# RK3399_EMMC_ADC_PCIE.net
KiCad netlist of a schematic drawn in Altium Designer
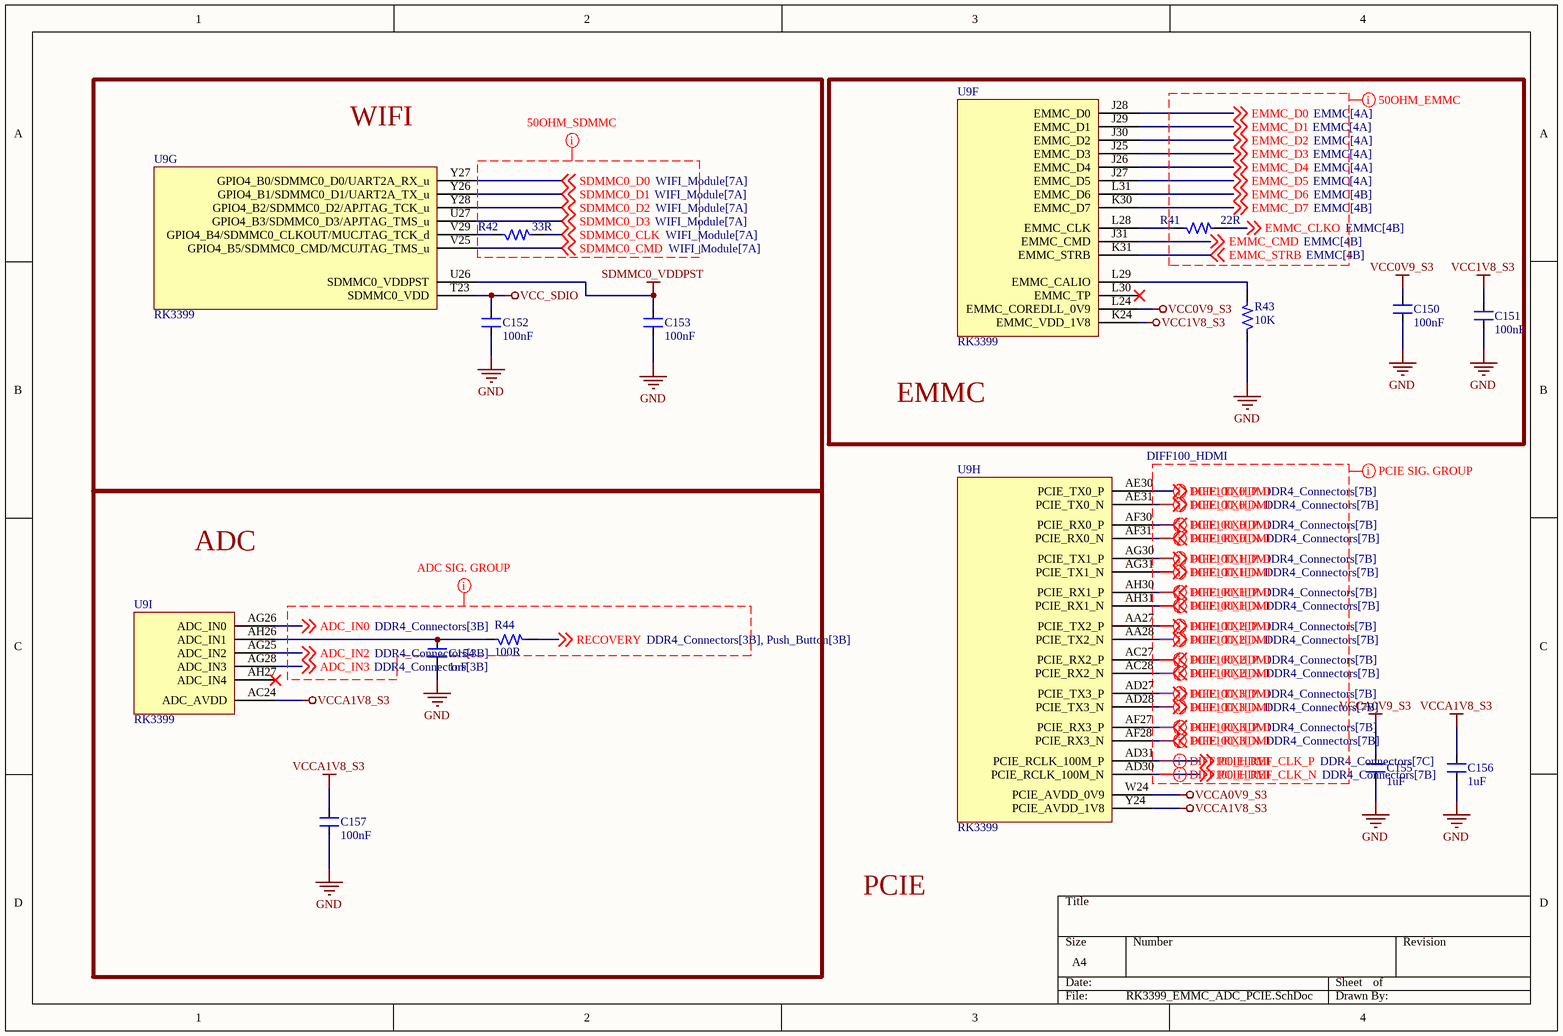
[diagram p0: RK3399_EMMC_ADC_PCIE.SchDoc]

(export (version "E")
  (design (tool "Eeschema 10.0.6"))
  (components
    (comp (ref "C150")
      (value "100nF")
      (footprint "CAP_0201")
      (description "0.1µF ±10% 25V Ceramic Capacitor X5R 0201 (0603 Metric)")
      (fields
        (field (name "MANUFACTURER") "TDK Corporation")
        (field (name "MANUFACTURER PART NUMBER") "C0603X5R1E104K030BB")
      )
      (libsource (lib "EsteemPCB_SOM_Course_schlib") (part "CAP_100nF-25V-10%-0201"))
    )
    (comp (ref "C151")
      (value "100nF")
      (footprint "CAP_0201")
      (description "0.1µF ±10% 25V Ceramic Capacitor X5R 0201 (0603 Metric)")
      (fields
        (field (name "MANUFACTURER") "TDK Corporation")
        (field (name "MANUFACTURER PART NUMBER") "C0603X5R1E104K030BB")
      )
      (libsource (lib "EsteemPCB_SOM_Course_schlib") (part "CAP_100nF-25V-10%-0201"))
    )
    (comp (ref "C152")
      (value "100nF")
      (footprint "CAP_0201")
      (description "0.1µF ±10% 25V Ceramic Capacitor X5R 0201 (0603 Metric)")
      (fields
        (field (name "MANUFACTURER") "TDK Corporation")
        (field (name "MANUFACTURER PART NUMBER") "C0603X5R1E104K030BB")
      )
      (libsource (lib "EsteemPCB_SOM_Course_schlib") (part "CAP_100nF-25V-10%-0201"))
    )
    (comp (ref "C153")
      (value "100nF")
      (footprint "CAP_0201")
      (description "0.1µF ±10% 25V Ceramic Capacitor X5R 0201 (0603 Metric)")
      (fields
        (field (name "MANUFACTURER") "TDK Corporation")
        (field (name "MANUFACTURER PART NUMBER") "C0603X5R1E104K030BB")
      )
      (libsource (lib "EsteemPCB_SOM_Course_schlib") (part "CAP_100nF-25V-10%-0201"))
    )
    (comp (ref "C154")
      (value "1nF")
      (footprint "CAP_0201")
      (description "1000pF ±10% 16V Ceramic Capacitor X7R 0201 (0603 Metric)")
      (fields
        (field (name "MANUFACTURER") "Murata Electronics")
        (field (name "MANUFACTURER PART NUMBER") "GRM033R71C102KA01D")
      )
      (libsource (lib "EsteemPCB_SOM_Course_schlib") (part "CAP_1nF-16V-10%-0201"))
    )
    (comp (ref "C155")
      (value "1uF")
      (footprint "CAP_0201")
      (description "1µF ±20% 16V Ceramic Capacitor X5R 0201 (0603 Metric)")
      (fields
        (field (name "MANUFACTURER") "Samsung Electro-Mechanics")
        (field (name "MANUFACTURER PART NUMBER") "CL03A105MO3NRNH")
      )
      (libsource (lib "EsteemPCB_SOM_Course_schlib") (part "CAP_1uF-16V-10%-0201"))
    )
    (comp (ref "C156")
      (value "1uF")
      (footprint "CAP_0201")
      (description "1µF ±20% 16V Ceramic Capacitor X5R 0201 (0603 Metric)")
      (fields
        (field (name "MANUFACTURER") "Samsung Electro-Mechanics")
        (field (name "MANUFACTURER PART NUMBER") "CL03A105MO3NRNH")
      )
      (libsource (lib "EsteemPCB_SOM_Course_schlib") (part "CAP_1uF-16V-10%-0201"))
    )
    (comp (ref "C157")
      (value "100nF")
      (footprint "CAP_0201")
      (description "0.1µF ±10% 25V Ceramic Capacitor X5R 0201 (0603 Metric)")
      (fields
        (field (name "MANUFACTURER") "TDK Corporation")
        (field (name "MANUFACTURER PART NUMBER") "C0603X5R1E104K030BB")
      )
      (libsource (lib "EsteemPCB_SOM_Course_schlib") (part "CAP_100nF-25V-10%-0201"))
    )
    (comp (ref "R41")
      (value "22R")
      (footprint "RES_0201")
      (description "22 Ohms ±1% 0.05W, 1/20W Chip Resistor 0201 (0603 Metric) Moisture Resistant Thick Film")
      (fields
        (field (name "MANUFACTURER") "Yageo")
        (field (name "MANUFACTURER PART NUMBER") "RC0201FR-0722RL")
      )
      (libsource (lib "EsteemPCB_SOM_Course_schlib") (part "RES_22R-0.05W-1%-0201"))
    )
    (comp (ref "R42")
      (value "33R")
      (footprint "RES_0201")
      (description "33 Ohms ±1% 0.05W, 1/20W Chip Resistor 0201 (0603 Metric) Thick Film")
      (fields
        (field (name "MANUFACTURER") "Yageo")
        (field (name "MANUFACTURER PART NUMBER") "RC0201FR-0733RL")
      )
      (libsource (lib "EsteemPCB_SOM_Course_schlib") (part "RES_33R-0.05W-1%-0201"))
    )
    (comp (ref "R43")
      (value "10K")
      (footprint "RES_0201")
      (description "10 kOhms ±1% 0.05W, 1/20W Chip Resistor 0201 (0603 Metric) Thick Film")
      (fields
        (field (name "MANUFACTURER") "Stackpole Electronics Inc")
        (field (name "MANUFACTURER PART NUMBER") "RMCF0201FT10K0")
      )
      (libsource (lib "EsteemPCB_SOM_Course_schlib") (part "RES_10K-0.05W-1%-0201"))
    )
    (comp (ref "R44")
      (value "100R")
      (footprint "RES_0201")
      (description "100 kOhms ±1% 0.05W, 1/20W Chip Resistor 0201 (0603 Metric) Automotive AEC-Q200 Thick Film")
      (fields
        (field (name "MANUFACTURER") "Panasonic Electronic Components")
        (field (name "MANUFACTURER PART NUMBER") "ERJ-1GNF1003C")
      )
      (libsource (lib "EsteemPCB_SOM_Course_schlib") (part "RES_100R-0.05W-1%-0201"))
    )
    (comp (ref "U9")
      (value "RK3399")
      (footprint "FBGA828_23_826X826")
      (description "RK3399 is a low power, high performance processor for computing, personal mobile.")
      (fields (field (name "MANUFACTURER") "Rockchip"))
      (libsource (lib "EsteemPCB_SOM_Course_schlib") (part "IC_RK3399-FCBGA828"))
    )
  )
  (nets
    (net (code "1") (name "ADC_IN0") (class "Default")
      (node (ref "U9") (pin "AG26") (pinfunction "ADC_IN0_AG26") (pintype "passive"))
    )
    (net (code "2") (name "ADC_IN2") (class "Default")
      (node (ref "U9") (pin "AG25") (pinfunction "ADC_IN2_AG25") (pintype "passive"))
    )
    (net (code "3") (name "ADC_IN3") (class "Default")
      (node (ref "U9") (pin "AG28") (pinfunction "ADC_IN3_AG28") (pintype "passive"))
    )
    (net (code "4") (name "EMMC_CLKO") (class "Default")
      (node (ref "R41") (pin "2") (pinfunction "2_2") (pintype "passive"))
    )
    (net (code "5") (name "EMMC_CMD") (class "Default")
      (node (ref "U9") (pin "J31") (pinfunction "EMMC_CMD_J31") (pintype "passive"))
    )
    (net (code "6") (name "EMMC_D0") (class "Default")
      (node (ref "U9") (pin "J28") (pinfunction "EMMC_D0_J28") (pintype "passive"))
    )
    (net (code "7") (name "EMMC_D1") (class "Default")
      (node (ref "U9") (pin "J29") (pinfunction "EMMC_D1_J29") (pintype "passive"))
    )
    (net (code "8") (name "EMMC_D2") (class "Default")
      (node (ref "U9") (pin "J30") (pinfunction "EMMC_D2_J30") (pintype "passive"))
    )
    (net (code "9") (name "EMMC_D3") (class "Default")
      (node (ref "U9") (pin "J25") (pinfunction "EMMC_D3_J25") (pintype "passive"))
    )
    (net (code "10") (name "EMMC_D4") (class "Default")
      (node (ref "U9") (pin "J26") (pinfunction "EMMC_D4_J26") (pintype "passive"))
    )
    (net (code "11") (name "EMMC_D5") (class "Default")
      (node (ref "U9") (pin "J27") (pinfunction "EMMC_D5_J27") (pintype "passive"))
    )
    (net (code "12") (name "EMMC_D6") (class "Default")
      (node (ref "U9") (pin "L31") (pinfunction "EMMC_D6_L31") (pintype "passive"))
    )
    (net (code "13") (name "EMMC_D7") (class "Default")
      (node (ref "U9") (pin "K30") (pinfunction "EMMC_D7_K30") (pintype "passive"))
    )
    (net (code "14") (name "EMMC_STRB") (class "Default")
      (node (ref "U9") (pin "K31") (pinfunction "EMMC_STRB_K31") (pintype "passive"))
    )
    (net (code "15") (name "GND") (class "Default")
      (node (ref "C150") (pin "1") (pinfunction "1_1") (pintype "passive"))
      (node (ref "C151") (pin "1") (pinfunction "1_1") (pintype "passive"))
      (node (ref "C152") (pin "1") (pinfunction "1_1") (pintype "passive"))
      (node (ref "C153") (pin "1") (pinfunction "1_1") (pintype "passive"))
      (node (ref "C154") (pin "1") (pinfunction "1_1") (pintype "passive"))
      (node (ref "C155") (pin "1") (pinfunction "1_1") (pintype "passive"))
      (node (ref "C156") (pin "1") (pinfunction "1_1") (pintype "passive"))
      (node (ref "C157") (pin "1") (pinfunction "1_1") (pintype "passive"))
      (node (ref "R43") (pin "1") (pinfunction "1_1") (pintype "passive"))
    )
    (net (code "16") (name "Net-(U9F-EMMC_CALIO)") (class "Default")
      (node (ref "R43") (pin "2") (pinfunction "2_2") (pintype "passive"))
      (node (ref "U9") (pin "L29") (pinfunction "EMMC_CALIO_L29") (pintype "passive"))
    )
    (net (code "17") (name "Net-(U9F-EMMC_CLK)") (class "Default")
      (node (ref "R41") (pin "1") (pinfunction "1_1") (pintype "passive"))
      (node (ref "U9") (pin "L28") (pinfunction "EMMC_CLK_L28") (pintype "passive"))
    )
    (net (code "18") (name "Net-(U9G-GPIO4_B4{slash}SDMMC0_CLKOUT{slash}MUCJTAG_TCK_d)") (class "Default")
      (node (ref "R42") (pin "1") (pinfunction "1_1") (pintype "passive"))
      (node (ref "U9") (pin "V29") (pinfunction "GPIO4_B4/SDMMC0_CLKOUT/MUCJTAG_TCK_d_V29") (pintype "passive"))
    )
    (net (code "19") (name "Net-(U9I-ADC_IN1)") (class "Default")
      (node (ref "C154") (pin "2") (pinfunction "2_2") (pintype "passive"))
      (node (ref "R44") (pin "1") (pinfunction "1_1") (pintype "passive"))
      (node (ref "U9") (pin "AH26") (pinfunction "ADC_IN1_AH26") (pintype "passive"))
    )
    (net (code "20") (name "PCIE_REF_CLK_N") (class "Default")
      (node (ref "U9") (pin "AD30") (pinfunction "PCIE_RCLK_100M_N_AD30") (pintype "passive"))
    )
    (net (code "21") (name "PCIE_REF_CLK_P") (class "Default")
      (node (ref "U9") (pin "AD31") (pinfunction "PCIE_RCLK_100M_P_AD31") (pintype "passive"))
    )
    (net (code "22") (name "PCIE_RX0_N") (class "Default")
      (node (ref "U9") (pin "AF31") (pinfunction "PCIE_RX0_N_AF31") (pintype "passive"))
    )
    (net (code "23") (name "PCIE_RX0_P") (class "Default")
      (node (ref "U9") (pin "AF30") (pinfunction "PCIE_RX0_P_AF30") (pintype "passive"))
    )
    (net (code "24") (name "PCIE_RX1_N") (class "Default")
      (node (ref "U9") (pin "AH31") (pinfunction "PCIE_RX1_N_AH31") (pintype "passive"))
    )
    (net (code "25") (name "PCIE_RX1_P") (class "Default")
      (node (ref "U9") (pin "AH30") (pinfunction "PCIE_RX1_P_AH30") (pintype "passive"))
    )
    (net (code "26") (name "PCIE_RX2_N") (class "Default")
      (node (ref "U9") (pin "AC28") (pinfunction "PCIE_RX2_N_AC28") (pintype "passive"))
    )
    (net (code "27") (name "PCIE_RX2_P") (class "Default")
      (node (ref "U9") (pin "AC27") (pinfunction "PCIE_RX2_P_AC27") (pintype "passive"))
    )
    (net (code "28") (name "PCIE_RX3_N") (class "Default")
      (node (ref "U9") (pin "AF28") (pinfunction "PCIE_RX3_N_AF28") (pintype "passive"))
    )
    (net (code "29") (name "PCIE_RX3_P") (class "Default")
      (node (ref "U9") (pin "AF27") (pinfunction "PCIE_RX3_P_AF27") (pintype "passive"))
    )
    (net (code "30") (name "PCIE_TX0_N") (class "Default")
      (node (ref "U9") (pin "AE31") (pinfunction "PCIE_TX0_N_AE31") (pintype "passive"))
    )
    (net (code "31") (name "PCIE_TX0_P") (class "Default")
      (node (ref "U9") (pin "AE30") (pinfunction "PCIE_TX0_P_AE30") (pintype "passive"))
    )
    (net (code "32") (name "PCIE_TX1_N") (class "Default")
      (node (ref "U9") (pin "AG31") (pinfunction "PCIE_TX1_N_AG31") (pintype "passive"))
    )
    (net (code "33") (name "PCIE_TX1_P") (class "Default")
      (node (ref "U9") (pin "AG30") (pinfunction "PCIE_TX1_P_AG30") (pintype "passive"))
    )
    (net (code "34") (name "PCIE_TX2_N") (class "Default")
      (node (ref "U9") (pin "AA28") (pinfunction "PCIE_TX2_N_AA28") (pintype "passive"))
    )
    (net (code "35") (name "PCIE_TX2_P") (class "Default")
      (node (ref "U9") (pin "AA27") (pinfunction "PCIE_TX2_P_AA27") (pintype "passive"))
    )
    (net (code "36") (name "PCIE_TX3_N") (class "Default")
      (node (ref "U9") (pin "AD28") (pinfunction "PCIE_TX3_N_AD28") (pintype "passive"))
    )
    (net (code "37") (name "PCIE_TX3_P") (class "Default")
      (node (ref "U9") (pin "AD27") (pinfunction "PCIE_TX3_P_AD27") (pintype "passive"))
    )
    (net (code "38") (name "RECOVERY") (class "Default")
      (node (ref "R44") (pin "2") (pinfunction "2_2") (pintype "passive"))
    )
    (net (code "39") (name "SDMMC0_CLK") (class "Default")
      (node (ref "R42") (pin "2") (pinfunction "2_2") (pintype "passive"))
    )
    (net (code "40") (name "SDMMC0_CMD") (class "Default")
      (node (ref "U9") (pin "V25") (pinfunction "GPIO4_B5/SDMMC0_CMD/MCUJTAG_TMS_u_V25") (pintype "passive"))
    )
    (net (code "41") (name "SDMMC0_D0") (class "Default")
      (node (ref "U9") (pin "Y27") (pinfunction "GPIO4_B0/SDMMC0_D0/UART2A_RX_u_Y27") (pintype "passive"))
    )
    (net (code "42") (name "SDMMC0_D1") (class "Default")
      (node (ref "U9") (pin "Y26") (pinfunction "GPIO4_B1/SDMMC0_D1/UART2A_TX_u_Y26") (pintype "passive"))
    )
    (net (code "43") (name "SDMMC0_D2") (class "Default")
      (node (ref "U9") (pin "Y28") (pinfunction "GPIO4_B2/SDMMC0_D2/APJTAG_TCK_u_Y28") (pintype "passive"))
    )
    (net (code "44") (name "SDMMC0_D3") (class "Default")
      (node (ref "U9") (pin "U27") (pinfunction "GPIO4_B3/SDMMC0_D3/APJTAG_TMS_u_U27") (pintype "passive"))
    )
    (net (code "45") (name "SDMMC0_VDDPST") (class "Default")
      (node (ref "C153") (pin "2") (pinfunction "2_2") (pintype "passive"))
      (node (ref "U9") (pin "U26") (pinfunction "SDMMC0_VDDPST_U26") (pintype "passive"))
    )
    (net (code "46") (name "VCC0V9_S3") (class "Default")
      (node (ref "C150") (pin "2") (pinfunction "2_2") (pintype "passive"))
      (node (ref "U9") (pin "L24") (pinfunction "EMMC_COREDLL_0V9_L24") (pintype "passive"))
    )
    (net (code "47") (name "VCC1V8_S3") (class "Default")
      (node (ref "C151") (pin "2") (pinfunction "2_2") (pintype "passive"))
      (node (ref "U9") (pin "K24") (pinfunction "EMMC_VDD_1V8_K24") (pintype "passive"))
    )
    (net (code "48") (name "VCCA0V9_S3") (class "Default")
      (node (ref "C155") (pin "2") (pinfunction "2_2") (pintype "passive"))
      (node (ref "U9") (pin "W24") (pinfunction "PCIE_AVDD_0V9_W24") (pintype "passive"))
    )
    (net (code "49") (name "VCCA1V8_S3") (class "Default")
      (node (ref "C156") (pin "2") (pinfunction "2_2") (pintype "passive"))
      (node (ref "C157") (pin "2") (pinfunction "2_2") (pintype "passive"))
      (node (ref "U9") (pin "AC24") (pinfunction "ADC_AVDD_AC24") (pintype "passive"))
      (node (ref "U9") (pin "Y24") (pinfunction "PCIE_AVDD_1V8_Y24") (pintype "passive"))
    )
    (net (code "50") (name "VCC_SDIO") (class "Default")
      (node (ref "C152") (pin "2") (pinfunction "2_2") (pintype "passive"))
      (node (ref "U9") (pin "T23") (pinfunction "SDMMC0_VDD_T23") (pintype "passive"))
    )
    (net (code "51") (name "unconnected-(U9F-EMMC_TP-PadL30)") (class "Default")
      (node (ref "U9") (pin "L30") (pinfunction "EMMC_TP_L30") (pintype "passive+no_connect"))
    )
    (net (code "52") (name "unconnected-(U9I-ADC_IN4-PadAH27)") (class "Default")
      (node (ref "U9") (pin "AH27") (pinfunction "ADC_IN4_AH27") (pintype "passive+no_connect"))
    )
  )
)
